# Power.net
KiCad netlist of a schematic drawn in Altium Designer
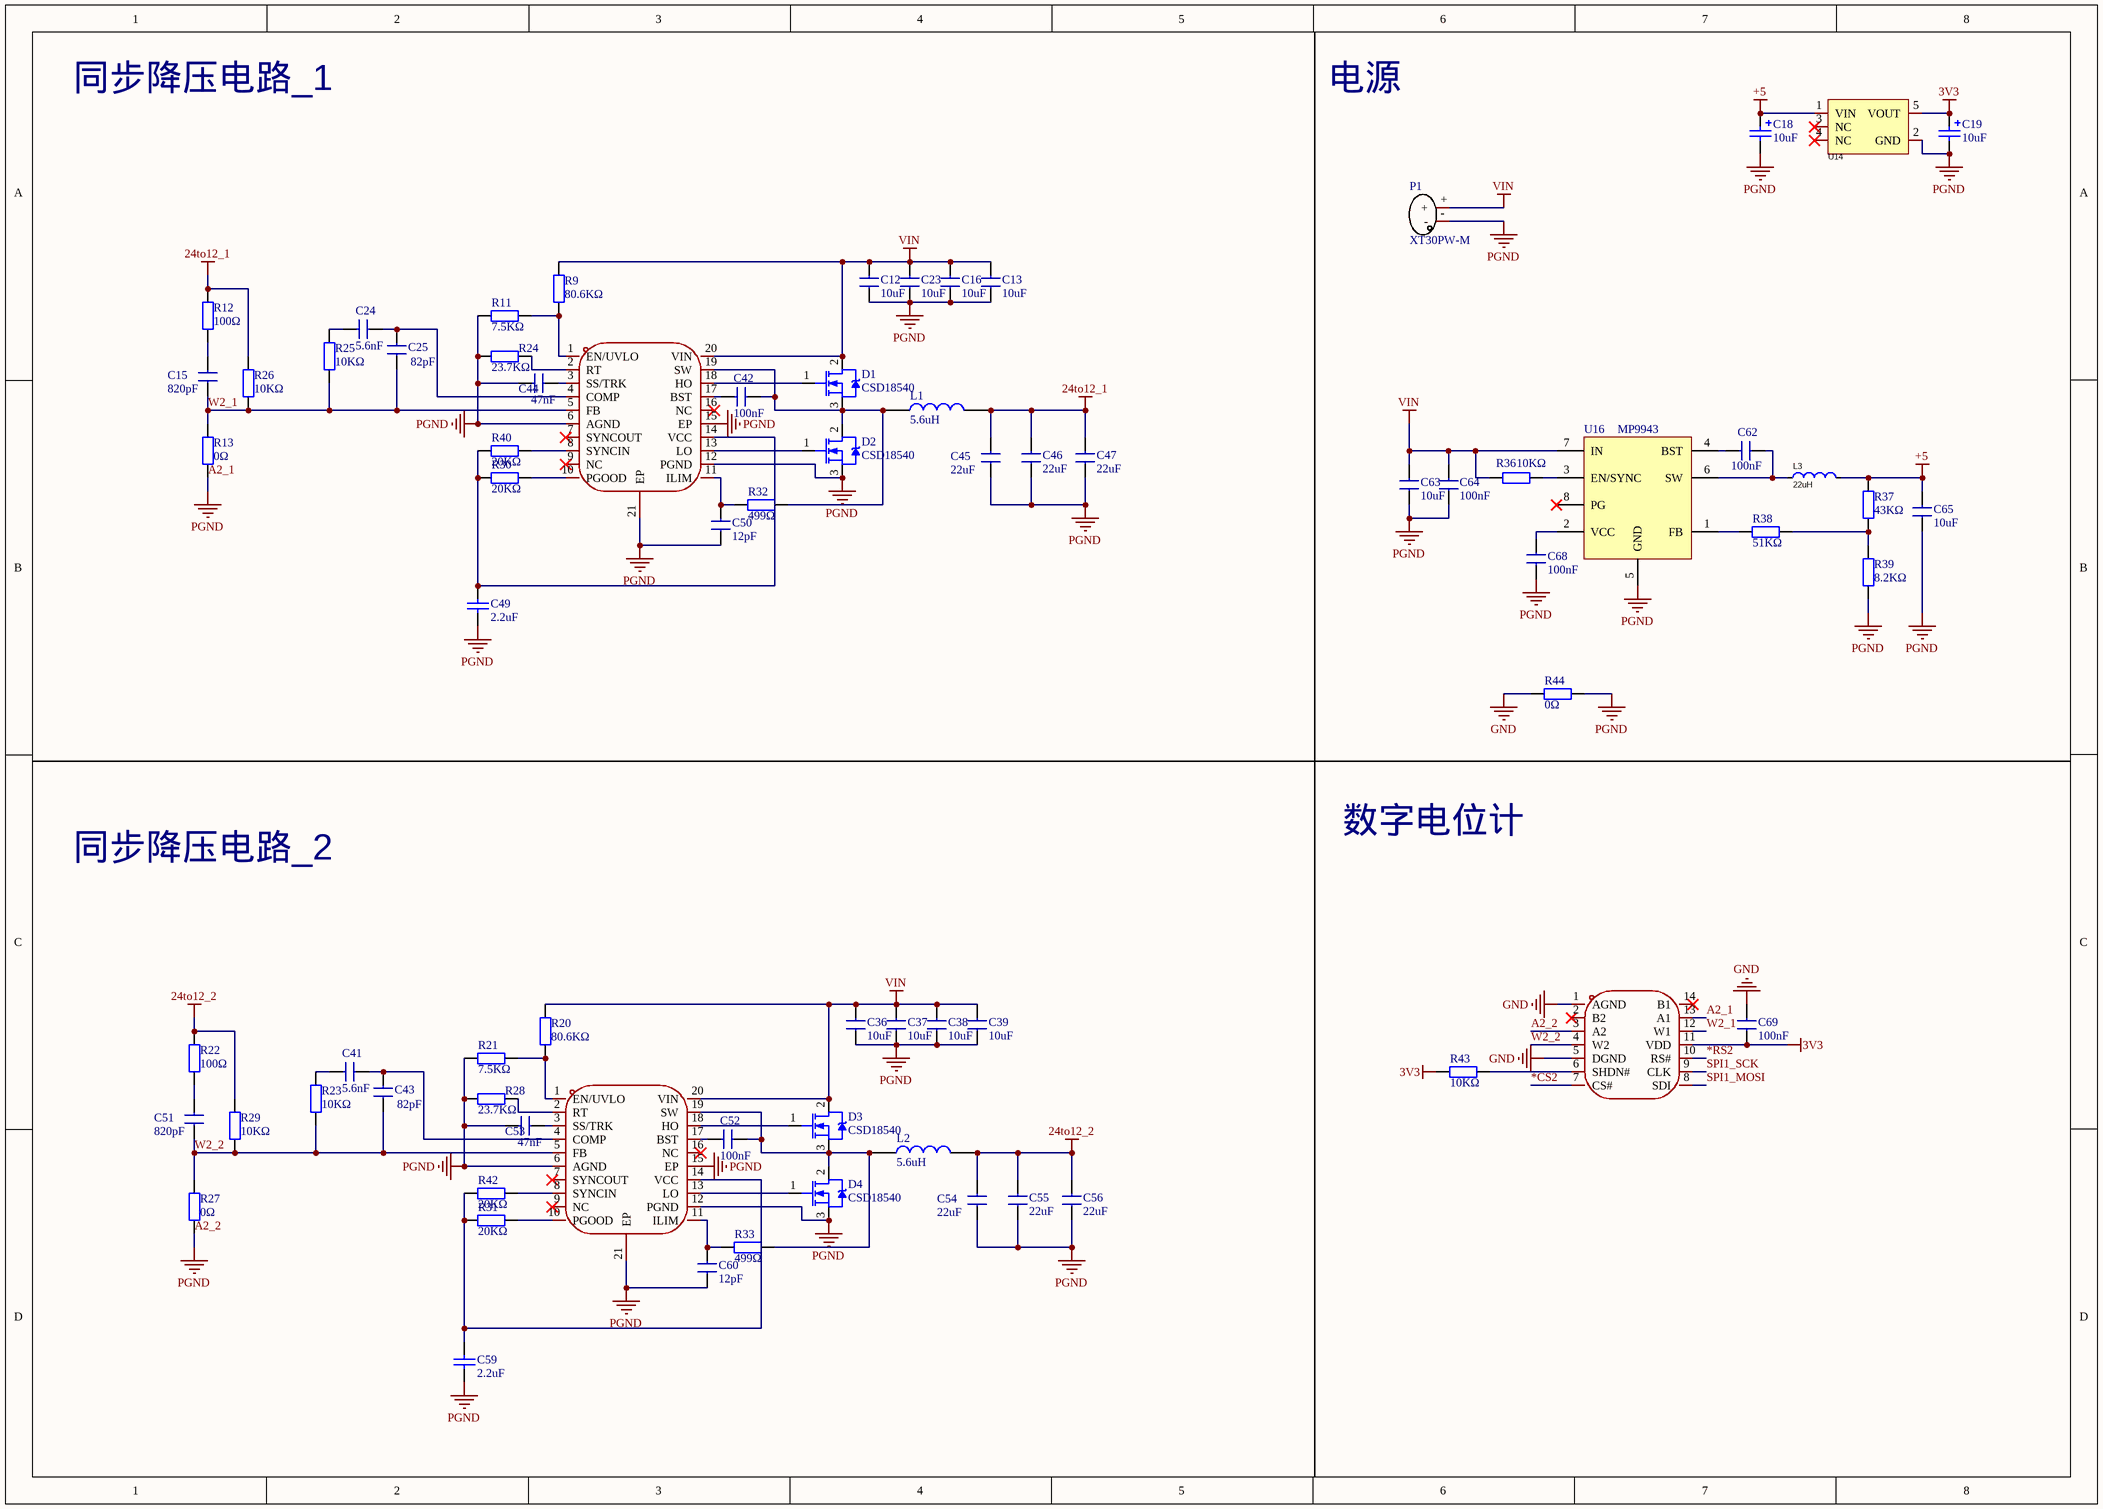
[diagram p0: Power.SchDoc]

(export (version "E")
  (design (tool "Eeschema 10.0.6"))
  (components
    (comp (ref "C12")
      (value "10uF")
      (footprint "1210")
      (description "1210贴片电容")
      (libsource (lib "Integrated_Library1") (part "1210贴片电容"))
    )
    (comp (ref "C13")
      (value "10uF")
      (footprint "1210")
      (description "1210贴片电容")
      (libsource (lib "En") (part "1210贴片电容"))
    )
    (comp (ref "C15")
      (value "820pF")
      (footprint "c0402")
      (description "贴片电容0402")
      (libsource (lib "Integrated_Library1") (part "0402贴片电容"))
    )
    (comp (ref "C16")
      (value "10uF")
      (footprint "1210")
      (description "1210贴片电容")
      (libsource (lib "En") (part "1210贴片电容"))
    )
    (comp (ref "C18")
      (value "10uF")
      (footprint "3216")
      (description "3216钽电容")
      (libsource (lib "Integrated_Library1") (part "3216钽电容"))
    )
    (comp (ref "C19")
      (value "10uF")
      (footprint "3216")
      (description "3216钽电容")
      (libsource (lib "Integrated_Library1") (part "3216钽电容"))
    )
    (comp (ref "C23")
      (value "10uF")
      (footprint "1210")
      (description "1210贴片电容")
      (libsource (lib "En") (part "1210贴片电容"))
    )
    (comp (ref "C24")
      (value "5.6nF")
      (footprint "c0402")
      (description "贴片电容0402")
      (libsource (lib "Integrated_Library1") (part "0402贴片电容"))
    )
    (comp (ref "C25")
      (value "82pF")
      (footprint "c0402")
      (description "贴片电容0402")
      (libsource (lib "Integrated_Library1") (part "0402贴片电容"))
    )
    (comp (ref "C36")
      (value "10uF")
      (footprint "1210")
      (description "1210贴片电容")
      (libsource (lib "Integrated_Library1") (part "1210贴片电容"))
    )
    (comp (ref "C37")
      (value "10uF")
      (footprint "1210")
      (description "1210贴片电容")
      (libsource (lib "En") (part "1210贴片电容"))
    )
    (comp (ref "C38")
      (value "10uF")
      (footprint "1210")
      (description "1210贴片电容")
      (libsource (lib "En") (part "1210贴片电容"))
    )
    (comp (ref "C39")
      (value "10uF")
      (footprint "1210")
      (description "1210贴片电容")
      (libsource (lib "En") (part "1210贴片电容"))
    )
    (comp (ref "C41")
      (value "5.6nF")
      (footprint "c0402")
      (description "贴片电容0402")
      (libsource (lib "Integrated_Library1") (part "0402贴片电容"))
    )
    (comp (ref "C42")
      (value "100nF")
      (footprint "C 0603_M")
      (description "贴片电容0402")
      (libsource (lib "Integrated_Library1") (part "0402贴片电容"))
    )
    (comp (ref "C43")
      (value "82pF")
      (footprint "c0402")
      (description "贴片电容0402")
      (libsource (lib "Integrated_Library1") (part "0402贴片电容"))
    )
    (comp (ref "C44")
      (value "47nF")
      (footprint "c0402")
      (description "贴片电容0402")
      (libsource (lib "Integrated_Library1") (part "0402贴片电容"))
    )
    (comp (ref "C45")
      (value "22uF")
      (footprint "1210")
      (description "1210贴片电容")
      (libsource (lib "En") (part "1210贴片电容"))
    )
    (comp (ref "C46")
      (value "22uF")
      (footprint "1210")
      (description "1210贴片电容")
      (libsource (lib "En") (part "1210贴片电容"))
    )
    (comp (ref "C47")
      (value "22uF")
      (footprint "1210")
      (description "1210贴片电容")
      (libsource (lib "En") (part "1210贴片电容"))
    )
    (comp (ref "C49")
      (value "2.2uF")
      (footprint "C 0603_M")
      (description "0603贴片电容")
      (libsource (lib "En") (part "0603贴片电容"))
    )
    (comp (ref "C50")
      (value "12pF")
      (footprint "c0402")
      (description "贴片电容0402")
      (libsource (lib "Integrated_Library1") (part "0402贴片电容"))
    )
    (comp (ref "C51")
      (value "820pF")
      (footprint "c0402")
      (description "贴片电容0402")
      (libsource (lib "Integrated_Library1") (part "0402贴片电容"))
    )
    (comp (ref "C52")
      (value "100nF")
      (footprint "C 0603_M")
      (description "贴片电容0402")
      (libsource (lib "Integrated_Library1") (part "0402贴片电容"))
    )
    (comp (ref "C53")
      (value "47nF")
      (footprint "c0402")
      (description "贴片电容0402")
      (libsource (lib "Integrated_Library1") (part "0402贴片电容"))
    )
    (comp (ref "C54")
      (value "22uF")
      (footprint "1210")
      (description "1210贴片电容")
      (libsource (lib "En") (part "1210贴片电容"))
    )
    (comp (ref "C55")
      (value "22uF")
      (footprint "1210")
      (description "1210贴片电容")
      (libsource (lib "En") (part "1210贴片电容"))
    )
    (comp (ref "C56")
      (value "22uF")
      (footprint "1210")
      (description "1210贴片电容")
      (libsource (lib "En") (part "1210贴片电容"))
    )
    (comp (ref "C59")
      (value "2.2uF")
      (footprint "C 0603_M")
      (description "0603贴片电容")
      (libsource (lib "En") (part "0603贴片电容"))
    )
    (comp (ref "C60")
      (value "12pF")
      (footprint "c0402")
      (description "贴片电容0402")
      (libsource (lib "Integrated_Library1") (part "0402贴片电容"))
    )
    (comp (ref "C62")
      (value "100nF")
      (footprint "c0402")
      (description "贴片电容0402")
      (libsource (lib "Integrated_Library1") (part "0402贴片电容"))
    )
    (comp (ref "C63")
      (value "10uF")
      (footprint "1210")
      (description "1210贴片电容")
      (libsource (lib "Integrated_Library1") (part "1210贴片电容"))
    )
    (comp (ref "C64")
      (value "100nF")
      (footprint "c0402")
      (description "贴片电容0402")
      (libsource (lib "Integrated_Library1") (part "0402贴片电容"))
    )
    (comp (ref "C65")
      (value "10uF")
      (footprint "1210")
      (description "1210贴片电容")
      (libsource (lib "Integrated_Library1") (part "1210贴片电容"))
    )
    (comp (ref "C68")
      (value "100nF")
      (footprint "c0402")
      (description "贴片电容0402")
      (libsource (lib "Integrated_Library1") (part "0402贴片电容"))
    )
    (comp (ref "C69")
      (value "100nF")
      (footprint "c0402")
      (description "贴片电容0402")
      (libsource (lib "Integrated_Library1") (part "0402贴片电容"))
    )
    (comp (ref "D1")
      (value "CSD18540")
      (footprint "pg-tdson-8")
      (description "N沟道MOS管")
      (fields (field (name "PUBLISHER") "Altium Limited"))
      (libsource (lib "En") (part "CSD18540"))
    )
    (comp (ref "D2")
      (value "CSD18540")
      (footprint "pg-tdson-8")
      (description "N沟道MOS管")
      (fields (field (name "PUBLISHER") "Altium Limited"))
      (libsource (lib "En") (part "CSD18540"))
    )
    (comp (ref "D3")
      (value "CSD18540")
      (footprint "pg-tdson-8")
      (description "N沟道MOS管")
      (fields (field (name "PUBLISHER") "Altium Limited"))
      (libsource (lib "En") (part "CSD18540"))
    )
    (comp (ref "D4")
      (value "CSD18540")
      (footprint "pg-tdson-8")
      (description "N沟道MOS管")
      (fields (field (name "PUBLISHER") "Altium Limited"))
      (libsource (lib "En") (part "CSD18540"))
    )
    (comp (ref "L1")
      (value "5.6uH")
      (footprint "L-SMD-0630")
      (description "一体成型屏蔽电感")
      (libsource (lib "En") (part "0630功率电感"))
    )
    (comp (ref "L2")
      (value "5.6uH")
      (footprint "L-SMD-0630")
      (description "一体成型屏蔽电感")
      (libsource (lib "En") (part "0630功率电感"))
    )
    (comp (ref "L3")
      (value "22uH")
      (footprint "IND-SMD_L5.4-W5.2")
      (description "一体成型屏蔽电感，0530封装，额定电流3A")
      (fields (field (name "MANUFACTURER") "XR(祥如)") (field (name "MANUFACTURER PART") "XR0530-100M"))
      (libsource (lib "En") (part "0530屏蔽电感"))
    )
    (comp (ref "P1")
      (value "XT30PW-M")
      (footprint "XT30PW-M")
      (description "卧式XT30母头")
      (fields (field (name "PUBLISHER") "Altium Limited"))
      (libsource (lib "Integrated_Library1") (part "卧式XT30母头"))
    )
    (comp (ref "R9")
      (value "80.6KΩ")
      (footprint "R0402")
      (description "0402贴片电阻")
      (libsource (lib "Integrated_Library1") (part "0402贴片电阻"))
    )
    (comp (ref "R11")
      (value "7.5KΩ")
      (footprint "R0402")
      (description "0402贴片电阻")
      (libsource (lib "") (part "0402贴片电阻_2"))
    )
    (comp (ref "R12")
      (value "100Ω")
      (footprint "R0402")
      (description "0402贴片电阻")
      (libsource (lib "") (part "0402贴片电阻_1"))
    )
    (comp (ref "R13")
      (value "0Ω")
      (footprint "R0402")
      (description "0402贴片电阻")
      (libsource (lib "Integrated_Library1") (part "0402贴片电阻"))
    )
    (comp (ref "R20")
      (value "80.6KΩ")
      (footprint "R0402")
      (description "0402贴片电阻")
      (libsource (lib "Integrated_Library1") (part "0402贴片电阻"))
    )
    (comp (ref "R21")
      (value "7.5KΩ")
      (footprint "R0402")
      (description "0402贴片电阻")
      (libsource (lib "") (part "0402贴片电阻_2"))
    )
    (comp (ref "R22")
      (value "100Ω")
      (footprint "R0402")
      (description "0402贴片电阻")
      (libsource (lib "") (part "0402贴片电阻_1"))
    )
    (comp (ref "R23")
      (value "10KΩ")
      (footprint "R0402")
      (description "0402贴片电阻")
      (libsource (lib "") (part "0402贴片电阻_1"))
    )
    (comp (ref "R24")
      (value "23.7KΩ")
      (footprint "R0402")
      (description "0402贴片电阻")
      (libsource (lib "") (part "0402贴片电阻_3"))
    )
    (comp (ref "R25")
      (value "10KΩ")
      (footprint "R0402")
      (description "0402贴片电阻")
      (libsource (lib "") (part "0402贴片电阻_1"))
    )
    (comp (ref "R26")
      (value "10KΩ")
      (footprint "R0402")
      (description "0402贴片电阻")
      (libsource (lib "") (part "0402贴片电阻_1"))
    )
    (comp (ref "R27")
      (value "0Ω")
      (footprint "R0402")
      (description "0402贴片电阻")
      (libsource (lib "Integrated_Library1") (part "0402贴片电阻"))
    )
    (comp (ref "R28")
      (value "23.7KΩ")
      (footprint "R0402")
      (description "0402贴片电阻")
      (libsource (lib "") (part "0402贴片电阻_3"))
    )
    (comp (ref "R29")
      (value "10KΩ")
      (footprint "R0402")
      (description "0402贴片电阻")
      (libsource (lib "") (part "0402贴片电阻_1"))
    )
    (comp (ref "R30")
      (value "20KΩ")
      (footprint "R0402")
      (description "0402贴片电阻")
      (libsource (lib "") (part "0402贴片电阻_3"))
    )
    (comp (ref "R31")
      (value "20KΩ")
      (footprint "R0402")
      (description "0402贴片电阻")
      (libsource (lib "") (part "0402贴片电阻_3"))
    )
    (comp (ref "R32")
      (value "499Ω")
      (footprint "R0402")
      (description "0402贴片电阻")
      (libsource (lib "") (part "0402贴片电阻_3"))
    )
    (comp (ref "R33")
      (value "499Ω")
      (footprint "R0402")
      (description "0402贴片电阻")
      (libsource (lib "") (part "0402贴片电阻_3"))
    )
    (comp (ref "R36")
      (value "10KΩ")
      (footprint "R0402")
      (description "0402贴片电阻")
      (libsource (lib "") (part "0402贴片电阻_2"))
    )
    (comp (ref "R37")
      (value "43KΩ")
      (footprint "R0402")
      (description "0402贴片电阻")
      (libsource (lib "") (part "0402贴片电阻_1"))
    )
    (comp (ref "R38")
      (value "51KΩ")
      (footprint "R0402")
      (description "0402贴片电阻")
      (libsource (lib "") (part "0402贴片电阻_2"))
    )
    (comp (ref "R39")
      (value "8.2KΩ")
      (footprint "R0402")
      (description "0402贴片电阻")
      (libsource (lib "") (part "0402贴片电阻_1"))
    )
    (comp (ref "R40")
      (value "20KΩ")
      (footprint "R0402")
      (description "0402贴片电阻")
      (libsource (lib "") (part "0402贴片电阻_3"))
    )
    (comp (ref "R42")
      (value "20KΩ")
      (footprint "R0402")
      (description "0402贴片电阻")
      (libsource (lib "") (part "0402贴片电阻_3"))
    )
    (comp (ref "R43")
      (value "10KΩ")
      (footprint "R0402")
      (description "0402贴片电阻")
      (libsource (lib "") (part "0402贴片电阻_3"))
    )
    (comp (ref "R44")
      (value "0Ω")
      (footprint "R0402")
      (description "0402贴片电阻")
      (libsource (lib "") (part "0402贴片电阻_2"))
    )
    (comp (ref "U7")
      (value "LM25145RGYR")
      (footprint "VQFN-20_L4.5-W3.5-P0.50-BL-EP")
      (fields (field (name "MANUFACTURER") "TI(德州仪器)"))
      (libsource (lib "Schlib1") (part "LM25145RGYR"))
    )
    (comp (ref "U13")
      (value "LM25145RGYR")
      (footprint "VQFN-20_L4.5-W3.5-P0.50-BL-EP")
      (fields (field (name "MANUFACTURER") "TI(德州仪器)"))
      (libsource (lib "Schlib1") (part "LM25145RGYR"))
    )
    (comp (ref "U14")
      (value "XC6201P332MR-HXY")
      (footprint "SOT-23-5_L3.0-W1.7-P0.95-LS2.8-BR")
      (description "3.3V LDO")
      (fields (field (name "MANUFACTURER") "HXY MOSFET(华轩阳电子)"))
      (libsource (lib "Integrated_Library1") (part "XC6201P332MR-HXY"))
    )
    (comp (ref "U16")
      (value "MP9943")
      (footprint "QFN-8 3x3")
      (libsource (lib "Integrated_Library1") (part "MP9943"))
    )
    (comp (ref "U17")
      (value "AD8402ARZ10-REEL")
      (footprint "SOIC-14_L8.7-W3.9-P1.27-LS6.0-BL")
      (fields (field (name "MANUFACTURER") "ADI(亚德诺)"))
      (libsource (lib "Schlib1") (part "AD8402ARZ10-REEL"))
    )
  )
  (nets
    (net (code "1") (name "+5") (class "Default")
      (node (ref "C18") (pin "1") (pinfunction "1_1") (pintype "passive"))
      (node (ref "C65") (pin "2") (pinfunction "2_2") (pintype "passive"))
      (node (ref "L3") (pin "2") (pinfunction "2_2") (pintype "passive"))
      (node (ref "R37") (pin "2") (pinfunction "2_2") (pintype "passive"))
      (node (ref "U14") (pin "1") (pinfunction "VIN_1") (pintype "passive"))
    )
    (net (code "2") (name "/*CS2") (class "Default")
      (node (ref "U17") (pin "7") (pinfunction "CS#_7") (pintype "passive"))
    )
    (net (code "3") (name "/*RS2") (class "Default")
      (node (ref "U17") (pin "10") (pinfunction "RS#_10") (pintype "passive"))
    )
    (net (code "4") (name "/SPI1_MOSI") (class "Default")
      (node (ref "U17") (pin "8") (pinfunction "SDI_8") (pintype "passive"))
    )
    (net (code "5") (name "/SPI1_SCK") (class "Default")
      (node (ref "U17") (pin "9") (pinfunction "CLK_9") (pintype "passive"))
    )
    (net (code "6") (name "/W2_1") (class "Default")
      (node (ref "C15") (pin "2") (pinfunction "2_2") (pintype "passive"))
      (node (ref "C25") (pin "1") (pinfunction "1_1") (pintype "passive"))
      (node (ref "R13") (pin "1") (pinfunction "1_1") (pintype "passive"))
      (node (ref "R25") (pin "1") (pinfunction "1_1") (pintype "passive"))
      (node (ref "R26") (pin "1") (pinfunction "1_1") (pintype "passive"))
      (node (ref "U13") (pin "5") (pinfunction "FB_5") (pintype "passive"))
      (node (ref "U17") (pin "12") (pinfunction "W1_12") (pintype "passive"))
    )
    (net (code "7") (name "/W2_2") (class "Default")
      (node (ref "C43") (pin "1") (pinfunction "1_1") (pintype "passive"))
      (node (ref "C51") (pin "2") (pinfunction "2_2") (pintype "passive"))
      (node (ref "R23") (pin "1") (pinfunction "1_1") (pintype "passive"))
      (node (ref "R27") (pin "1") (pinfunction "1_1") (pintype "passive"))
      (node (ref "R29") (pin "1") (pinfunction "1_1") (pintype "passive"))
      (node (ref "U17") (pin "4") (pinfunction "W2_4") (pintype "passive"))
      (node (ref "U7") (pin "5") (pinfunction "FB_5") (pintype "passive"))
    )
    (net (code "8") (name "3V3") (class "Default")
      (node (ref "C19") (pin "1") (pinfunction "1_1") (pintype "passive"))
      (node (ref "C69") (pin "2") (pinfunction "2_2") (pintype "passive"))
      (node (ref "R43") (pin "2") (pinfunction "2_2") (pintype "passive"))
      (node (ref "U14") (pin "5") (pinfunction "VOUT_5") (pintype "passive"))
      (node (ref "U17") (pin "11") (pinfunction "VDD_11") (pintype "passive"))
    )
    (net (code "9") (name "24to12_1") (class "Default")
      (node (ref "C45") (pin "2") (pinfunction "2_2") (pintype "passive"))
      (node (ref "C46") (pin "2") (pinfunction "2_2") (pintype "passive"))
      (node (ref "C47") (pin "2") (pinfunction "2_2") (pintype "passive"))
      (node (ref "L1") (pin "2") (pinfunction "2_2") (pintype "passive"))
      (node (ref "R12") (pin "2") (pinfunction "2_2") (pintype "passive"))
      (node (ref "R26") (pin "2") (pinfunction "2_2") (pintype "passive"))
    )
    (net (code "10") (name "24to12_2") (class "Default")
      (node (ref "C54") (pin "2") (pinfunction "2_2") (pintype "passive"))
      (node (ref "C55") (pin "2") (pinfunction "2_2") (pintype "passive"))
      (node (ref "C56") (pin "2") (pinfunction "2_2") (pintype "passive"))
      (node (ref "L2") (pin "2") (pinfunction "2_2") (pintype "passive"))
      (node (ref "R22") (pin "2") (pinfunction "2_2") (pintype "passive"))
      (node (ref "R29") (pin "2") (pinfunction "2_2") (pintype "passive"))
    )
    (net (code "11") (name "GND") (class "Default")
      (node (ref "C69") (pin "1") (pinfunction "1_1") (pintype "passive"))
      (node (ref "R44") (pin "1") (pinfunction "1_1") (pintype "passive"))
      (node (ref "U17") (pin "1") (pinfunction "AGND_1") (pintype "passive"))
      (node (ref "U17") (pin "5") (pinfunction "DGND_5") (pintype "passive"))
    )
    (net (code "12") (name "Net-(C15-Pad1)") (class "Default")
      (node (ref "C15") (pin "1") (pinfunction "1_1") (pintype "passive"))
      (node (ref "R12") (pin "1") (pinfunction "1_1") (pintype "passive"))
    )
    (net (code "13") (name "Net-(C24-Pad2)") (class "Default")
      (node (ref "C24") (pin "2") (pinfunction "2_2") (pintype "passive"))
      (node (ref "R25") (pin "2") (pinfunction "2_2") (pintype "passive"))
    )
    (net (code "14") (name "Net-(C41-Pad2)") (class "Default")
      (node (ref "C41") (pin "2") (pinfunction "2_2") (pintype "passive"))
      (node (ref "R23") (pin "2") (pinfunction "2_2") (pintype "passive"))
    )
    (net (code "15") (name "Net-(C51-Pad1)") (class "Default")
      (node (ref "C51") (pin "1") (pinfunction "1_1") (pintype "passive"))
      (node (ref "R22") (pin "1") (pinfunction "1_1") (pintype "passive"))
    )
    (net (code "16") (name "Net-(D1-G)") (class "Default")
      (node (ref "D1") (pin "1") (pinfunction "G_1") (pintype "passive"))
      (node (ref "U13") (pin "18") (pinfunction "HO_18") (pintype "passive"))
    )
    (net (code "17") (name "Net-(D1-S)") (class "Default")
      (node (ref "C42") (pin "1") (pinfunction "1_1") (pintype "passive"))
      (node (ref "D1") (pin "3") (pinfunction "S_3") (pintype "passive"))
      (node (ref "D2") (pin "2") (pinfunction "D_2") (pintype "passive"))
      (node (ref "L1") (pin "1") (pinfunction "1_1") (pintype "passive"))
      (node (ref "R32") (pin "1") (pinfunction "1_1") (pintype "passive"))
      (node (ref "U13") (pin "19") (pinfunction "SW_19") (pintype "passive"))
    )
    (net (code "18") (name "Net-(D2-G)") (class "Default")
      (node (ref "D2") (pin "1") (pinfunction "G_1") (pintype "passive"))
      (node (ref "U13") (pin "13") (pinfunction "LO_13") (pintype "passive"))
    )
    (net (code "19") (name "Net-(D3-G)") (class "Default")
      (node (ref "D3") (pin "1") (pinfunction "G_1") (pintype "passive"))
      (node (ref "U7") (pin "18") (pinfunction "HO_18") (pintype "passive"))
    )
    (net (code "20") (name "Net-(D3-S)") (class "Default")
      (node (ref "C52") (pin "1") (pinfunction "1_1") (pintype "passive"))
      (node (ref "D3") (pin "3") (pinfunction "S_3") (pintype "passive"))
      (node (ref "D4") (pin "2") (pinfunction "D_2") (pintype "passive"))
      (node (ref "L2") (pin "1") (pinfunction "1_1") (pintype "passive"))
      (node (ref "R33") (pin "1") (pinfunction "1_1") (pintype "passive"))
      (node (ref "U7") (pin "19") (pinfunction "SW_19") (pintype "passive"))
    )
    (net (code "21") (name "Net-(D4-G)") (class "Default")
      (node (ref "D4") (pin "1") (pinfunction "G_1") (pintype "passive"))
      (node (ref "U7") (pin "13") (pinfunction "LO_13") (pintype "passive"))
    )
    (net (code "22") (name "Net-(R37-Pad1)") (class "Default")
      (node (ref "R37") (pin "1") (pinfunction "1_1") (pintype "passive"))
      (node (ref "R38") (pin "2") (pinfunction "2_2") (pintype "passive"))
      (node (ref "R39") (pin "2") (pinfunction "2_2") (pintype "passive"))
    )
    (net (code "23") (name "Net-(U7-BST)") (class "Default")
      (node (ref "C52") (pin "2") (pinfunction "2_2") (pintype "passive"))
      (node (ref "U7") (pin "17") (pinfunction "BST_17") (pintype "passive"))
    )
    (net (code "24") (name "Net-(U7-COMP)") (class "Default")
      (node (ref "C41") (pin "1") (pinfunction "1_1") (pintype "passive"))
      (node (ref "C43") (pin "2") (pinfunction "2_2") (pintype "passive"))
      (node (ref "U7") (pin "4") (pinfunction "COMP_4") (pintype "passive"))
    )
    (net (code "25") (name "Net-(U7-EN{slash}UVLO)") (class "Default")
      (node (ref "R20") (pin "2") (pinfunction "2_2") (pintype "passive"))
      (node (ref "R21") (pin "2") (pinfunction "2_2") (pintype "passive"))
      (node (ref "U7") (pin "1") (pinfunction "EN/UVLO_1") (pintype "passive"))
    )
    (net (code "26") (name "Net-(U7-ILIM)") (class "Default")
      (node (ref "C60") (pin "2") (pinfunction "2_2") (pintype "passive"))
      (node (ref "R33") (pin "2") (pinfunction "2_2") (pintype "passive"))
      (node (ref "U7") (pin "11") (pinfunction "ILIM_11") (pintype "passive"))
    )
    (net (code "27") (name "Net-(U7-PGOOD)") (class "Default")
      (node (ref "R31") (pin "1") (pinfunction "1_1") (pintype "passive"))
      (node (ref "U7") (pin "10") (pinfunction "PGOOD_10") (pintype "passive"))
    )
    (net (code "28") (name "Net-(U7-RT)") (class "Default")
      (node (ref "R28") (pin "1") (pinfunction "1_1") (pintype "passive"))
      (node (ref "U7") (pin "2") (pinfunction "RT_2") (pintype "passive"))
    )
    (net (code "29") (name "Net-(U7-SS{slash}TRK)") (class "Default")
      (node (ref "C53") (pin "1") (pinfunction "1_1") (pintype "passive"))
      (node (ref "U7") (pin "3") (pinfunction "SS/TRK_3") (pintype "passive"))
    )
    (net (code "30") (name "Net-(U7-SYNCIN)") (class "Default")
      (node (ref "R42") (pin "1") (pinfunction "1_1") (pintype "passive"))
      (node (ref "U7") (pin "8") (pinfunction "SYNCIN_8") (pintype "passive"))
    )
    (net (code "31") (name "Net-(U7-VCC)") (class "Default")
      (node (ref "C59") (pin "2") (pinfunction "2_2") (pintype "passive"))
      (node (ref "R31") (pin "2") (pinfunction "2_2") (pintype "passive"))
      (node (ref "R42") (pin "2") (pinfunction "2_2") (pintype "passive"))
      (node (ref "U7") (pin "14") (pinfunction "VCC_14") (pintype "passive"))
    )
    (net (code "32") (name "Net-(U13-BST)") (class "Default")
      (node (ref "C42") (pin "2") (pinfunction "2_2") (pintype "passive"))
      (node (ref "U13") (pin "17") (pinfunction "BST_17") (pintype "passive"))
    )
    (net (code "33") (name "Net-(U13-COMP)") (class "Default")
      (node (ref "C24") (pin "1") (pinfunction "1_1") (pintype "passive"))
      (node (ref "C25") (pin "2") (pinfunction "2_2") (pintype "passive"))
      (node (ref "U13") (pin "4") (pinfunction "COMP_4") (pintype "passive"))
    )
    (net (code "34") (name "Net-(U13-EN{slash}UVLO)") (class "Default")
      (node (ref "R11") (pin "2") (pinfunction "2_2") (pintype "passive"))
      (node (ref "R9") (pin "2") (pinfunction "2_2") (pintype "passive"))
      (node (ref "U13") (pin "1") (pinfunction "EN/UVLO_1") (pintype "passive"))
    )
    (net (code "35") (name "Net-(U13-ILIM)") (class "Default")
      (node (ref "C50") (pin "2") (pinfunction "2_2") (pintype "passive"))
      (node (ref "R32") (pin "2") (pinfunction "2_2") (pintype "passive"))
      (node (ref "U13") (pin "11") (pinfunction "ILIM_11") (pintype "passive"))
    )
    (net (code "36") (name "Net-(U13-PGOOD)") (class "Default")
      (node (ref "R30") (pin "1") (pinfunction "1_1") (pintype "passive"))
      (node (ref "U13") (pin "10") (pinfunction "PGOOD_10") (pintype "passive"))
    )
    (net (code "37") (name "Net-(U13-RT)") (class "Default")
      (node (ref "R24") (pin "1") (pinfunction "1_1") (pintype "passive"))
      (node (ref "U13") (pin "2") (pinfunction "RT_2") (pintype "passive"))
    )
    (net (code "38") (name "Net-(U13-SS{slash}TRK)") (class "Default")
      (node (ref "C44") (pin "1") (pinfunction "1_1") (pintype "passive"))
      (node (ref "U13") (pin "3") (pinfunction "SS/TRK_3") (pintype "passive"))
    )
    (net (code "39") (name "Net-(U13-SYNCIN)") (class "Default")
      (node (ref "R40") (pin "1") (pinfunction "1_1") (pintype "passive"))
      (node (ref "U13") (pin "8") (pinfunction "SYNCIN_8") (pintype "passive"))
    )
    (net (code "40") (name "Net-(U13-VCC)") (class "Default")
      (node (ref "C49") (pin "2") (pinfunction "2_2") (pintype "passive"))
      (node (ref "R30") (pin "2") (pinfunction "2_2") (pintype "passive"))
      (node (ref "R40") (pin "2") (pinfunction "2_2") (pintype "passive"))
      (node (ref "U13") (pin "14") (pinfunction "VCC_14") (pintype "passive"))
    )
    (net (code "41") (name "Net-(U16-BST)") (class "Default")
      (node (ref "C62") (pin "1") (pinfunction "1_1") (pintype "passive"))
      (node (ref "U16") (pin "4") (pinfunction "BST_4") (pintype "passive"))
    )
    (net (code "42") (name "Net-(U16-EN{slash}SYNC)") (class "Default")
      (node (ref "R36") (pin "2") (pinfunction "2_2") (pintype "passive"))
      (node (ref "U16") (pin "3") (pinfunction "EN/SYNC_3") (pintype "passive"))
    )
    (net (code "43") (name "Net-(U16-FB)") (class "Default")
      (node (ref "R38") (pin "1") (pinfunction "1_1") (pintype "passive"))
      (node (ref "U16") (pin "1") (pinfunction "FB_1") (pintype "passive"))
    )
    (net (code "44") (name "Net-(U16-SW)") (class "Default")
      (node (ref "C62") (pin "2") (pinfunction "2_2") (pintype "passive"))
      (node (ref "L3") (pin "1") (pinfunction "1_1") (pintype "passive"))
      (node (ref "U16") (pin "6") (pinfunction "SW_6") (pintype "passive"))
    )
    (net (code "45") (name "Net-(U16-VCC)") (class "Default")
      (node (ref "C68") (pin "2") (pinfunction "2_2") (pintype "passive"))
      (node (ref "U16") (pin "2") (pinfunction "VCC_2") (pintype "passive"))
    )
    (net (code "46") (name "Net-(U17-SHDN#)") (class "Default")
      (node (ref "R43") (pin "1") (pinfunction "1_1") (pintype "passive"))
      (node (ref "U17") (pin "6") (pinfunction "SHDN#_6") (pintype "passive"))
    )
    (net (code "47") (name "PGND") (class "Default")
      (node (ref "C12") (pin "1") (pinfunction "1_1") (pintype "passive"))
      (node (ref "C13") (pin "1") (pinfunction "1_1") (pintype "passive"))
      (node (ref "C16") (pin "1") (pinfunction "1_1") (pintype "passive"))
      (node (ref "C18") (pin "2") (pinfunction "2_2") (pintype "passive"))
      (node (ref "C19") (pin "2") (pinfunction "2_2") (pintype "passive"))
      (node (ref "C23") (pin "1") (pinfunction "1_1") (pintype "passive"))
      (node (ref "C36") (pin "1") (pinfunction "1_1") (pintype "passive"))
      (node (ref "C37") (pin "1") (pinfunction "1_1") (pintype "passive"))
      (node (ref "C38") (pin "1") (pinfunction "1_1") (pintype "passive"))
      (node (ref "C39") (pin "1") (pinfunction "1_1") (pintype "passive"))
      (node (ref "C44") (pin "2") (pinfunction "2_2") (pintype "passive"))
      (node (ref "C45") (pin "1") (pinfunction "1_1") (pintype "passive"))
      (node (ref "C46") (pin "1") (pinfunction "1_1") (pintype "passive"))
      (node (ref "C47") (pin "1") (pinfunction "1_1") (pintype "passive"))
      (node (ref "C49") (pin "1") (pinfunction "1_1") (pintype "passive"))
      (node (ref "C50") (pin "1") (pinfunction "1_1") (pintype "passive"))
      (node (ref "C53") (pin "2") (pinfunction "2_2") (pintype "passive"))
      (node (ref "C54") (pin "1") (pinfunction "1_1") (pintype "passive"))
      (node (ref "C55") (pin "1") (pinfunction "1_1") (pintype "passive"))
      (node (ref "C56") (pin "1") (pinfunction "1_1") (pintype "passive"))
      (node (ref "C59") (pin "1") (pinfunction "1_1") (pintype "passive"))
      (node (ref "C60") (pin "1") (pinfunction "1_1") (pintype "passive"))
      (node (ref "C63") (pin "1") (pinfunction "1_1") (pintype "passive"))
      (node (ref "C64") (pin "1") (pinfunction "1_1") (pintype "passive"))
      (node (ref "C65") (pin "1") (pinfunction "1_1") (pintype "passive"))
      (node (ref "C68") (pin "1") (pinfunction "1_1") (pintype "passive"))
      (node (ref "D2") (pin "3") (pinfunction "S_3") (pintype "passive"))
      (node (ref "D4") (pin "3") (pinfunction "S_3") (pintype "passive"))
      (node (ref "P1") (pin "-") (pinfunction "-_-") (pintype "passive"))
      (node (ref "R11") (pin "1") (pinfunction "1_1") (pintype "passive"))
      (node (ref "R13") (pin "2") (pinfunction "2_2") (pintype "passive"))
      (node (ref "R21") (pin "1") (pinfunction "1_1") (pintype "passive"))
      (node (ref "R24") (pin "2") (pinfunction "2_2") (pintype "passive"))
      (node (ref "R27") (pin "2") (pinfunction "2_2") (pintype "passive"))
      (node (ref "R28") (pin "2") (pinfunction "2_2") (pintype "passive"))
      (node (ref "R39") (pin "1") (pinfunction "1_1") (pintype "passive"))
      (node (ref "R44") (pin "2") (pinfunction "2_2") (pintype "passive"))
      (node (ref "U13") (pin "12") (pinfunction "PGND_12") (pintype "passive"))
      (node (ref "U13") (pin "15") (pinfunction "EP_15") (pintype "passive"))
      (node (ref "U13") (pin "21") (pinfunction "EP_21") (pintype "passive"))
      (node (ref "U13") (pin "6") (pinfunction "AGND_6") (pintype "passive"))
      (node (ref "U14") (pin "2") (pinfunction "GND_2") (pintype "passive"))
      (node (ref "U16") (pin "5") (pinfunction "GND_5") (pintype "passive"))
      (node (ref "U17") (pin "13") (pinfunction "A1_13") (pintype "passive"))
      (node (ref "U17") (pin "3") (pinfunction "A2_3") (pintype "passive"))
      (node (ref "U7") (pin "12") (pinfunction "PGND_12") (pintype "passive"))
      (node (ref "U7") (pin "15") (pinfunction "EP_15") (pintype "passive"))
      (node (ref "U7") (pin "21") (pinfunction "EP_21") (pintype "passive"))
      (node (ref "U7") (pin "6") (pinfunction "AGND_6") (pintype "passive"))
    )
    (net (code "48") (name "VIN") (class "Default")
      (node (ref "C12") (pin "2") (pinfunction "2_2") (pintype "passive"))
      (node (ref "C13") (pin "2") (pinfunction "2_2") (pintype "passive"))
      (node (ref "C16") (pin "2") (pinfunction "2_2") (pintype "passive"))
      (node (ref "C23") (pin "2") (pinfunction "2_2") (pintype "passive"))
      (node (ref "C36") (pin "2") (pinfunction "2_2") (pintype "passive"))
      (node (ref "C37") (pin "2") (pinfunction "2_2") (pintype "passive"))
      (node (ref "C38") (pin "2") (pinfunction "2_2") (pintype "passive"))
      (node (ref "C39") (pin "2") (pinfunction "2_2") (pintype "passive"))
      (node (ref "C63") (pin "2") (pinfunction "2_2") (pintype "passive"))
      (node (ref "C64") (pin "2") (pinfunction "2_2") (pintype "passive"))
      (node (ref "D1") (pin "2") (pinfunction "D_2") (pintype "passive"))
      (node (ref "D3") (pin "2") (pinfunction "D_2") (pintype "passive"))
      (node (ref "P1") (pin "+") (pinfunction "+_+") (pintype "passive"))
      (node (ref "R20") (pin "1") (pinfunction "1_1") (pintype "passive"))
      (node (ref "R36") (pin "1") (pinfunction "1_1") (pintype "passive"))
      (node (ref "R9") (pin "1") (pinfunction "1_1") (pintype "passive"))
      (node (ref "U13") (pin "20") (pinfunction "VIN_20") (pintype "passive"))
      (node (ref "U16") (pin "7") (pinfunction "IN_7") (pintype "passive"))
      (node (ref "U7") (pin "20") (pinfunction "VIN_20") (pintype "passive"))
    )
    (net (code "49") (name "unconnected-(U7-NC-Pad9)") (class "Default")
      (node (ref "U7") (pin "9") (pinfunction "NC_9") (pintype "passive+no_connect"))
    )
    (net (code "50") (name "unconnected-(U7-NC-Pad16)") (class "Default")
      (node (ref "U7") (pin "16") (pinfunction "NC_16") (pintype "passive+no_connect"))
    )
    (net (code "51") (name "unconnected-(U7-SYNCOUT-Pad7)") (class "Default")
      (node (ref "U7") (pin "7") (pinfunction "SYNCOUT_7") (pintype "passive+no_connect"))
    )
    (net (code "52") (name "unconnected-(U13-NC-Pad9)") (class "Default")
      (node (ref "U13") (pin "9") (pinfunction "NC_9") (pintype "passive+no_connect"))
    )
    (net (code "53") (name "unconnected-(U13-NC-Pad16)") (class "Default")
      (node (ref "U13") (pin "16") (pinfunction "NC_16") (pintype "passive+no_connect"))
    )
    (net (code "54") (name "unconnected-(U13-SYNCOUT-Pad7)") (class "Default")
      (node (ref "U13") (pin "7") (pinfunction "SYNCOUT_7") (pintype "passive+no_connect"))
    )
    (net (code "55") (name "unconnected-(U14-NC-Pad3)") (class "Default")
      (node (ref "U14") (pin "3") (pinfunction "NC_3") (pintype "passive+no_connect"))
    )
    (net (code "56") (name "unconnected-(U14-NC-Pad4)") (class "Default")
      (node (ref "U14") (pin "4") (pinfunction "NC_4") (pintype "passive+no_connect"))
    )
    (net (code "57") (name "unconnected-(U16-PG-Pad8)") (class "Default")
      (node (ref "U16") (pin "8") (pinfunction "PG_8") (pintype "passive+no_connect"))
    )
    (net (code "58") (name "unconnected-(U17-B1-Pad14)") (class "Default")
      (node (ref "U17") (pin "14") (pinfunction "B1_14") (pintype "passive+no_connect"))
    )
    (net (code "59") (name "unconnected-(U17-B2-Pad2)") (class "Default")
      (node (ref "U17") (pin "2") (pinfunction "B2_2") (pintype "passive+no_connect"))
    )
  )
)
